# interlock_circuit.net
KiCad netlist of a schematic drawn in Altium Designer
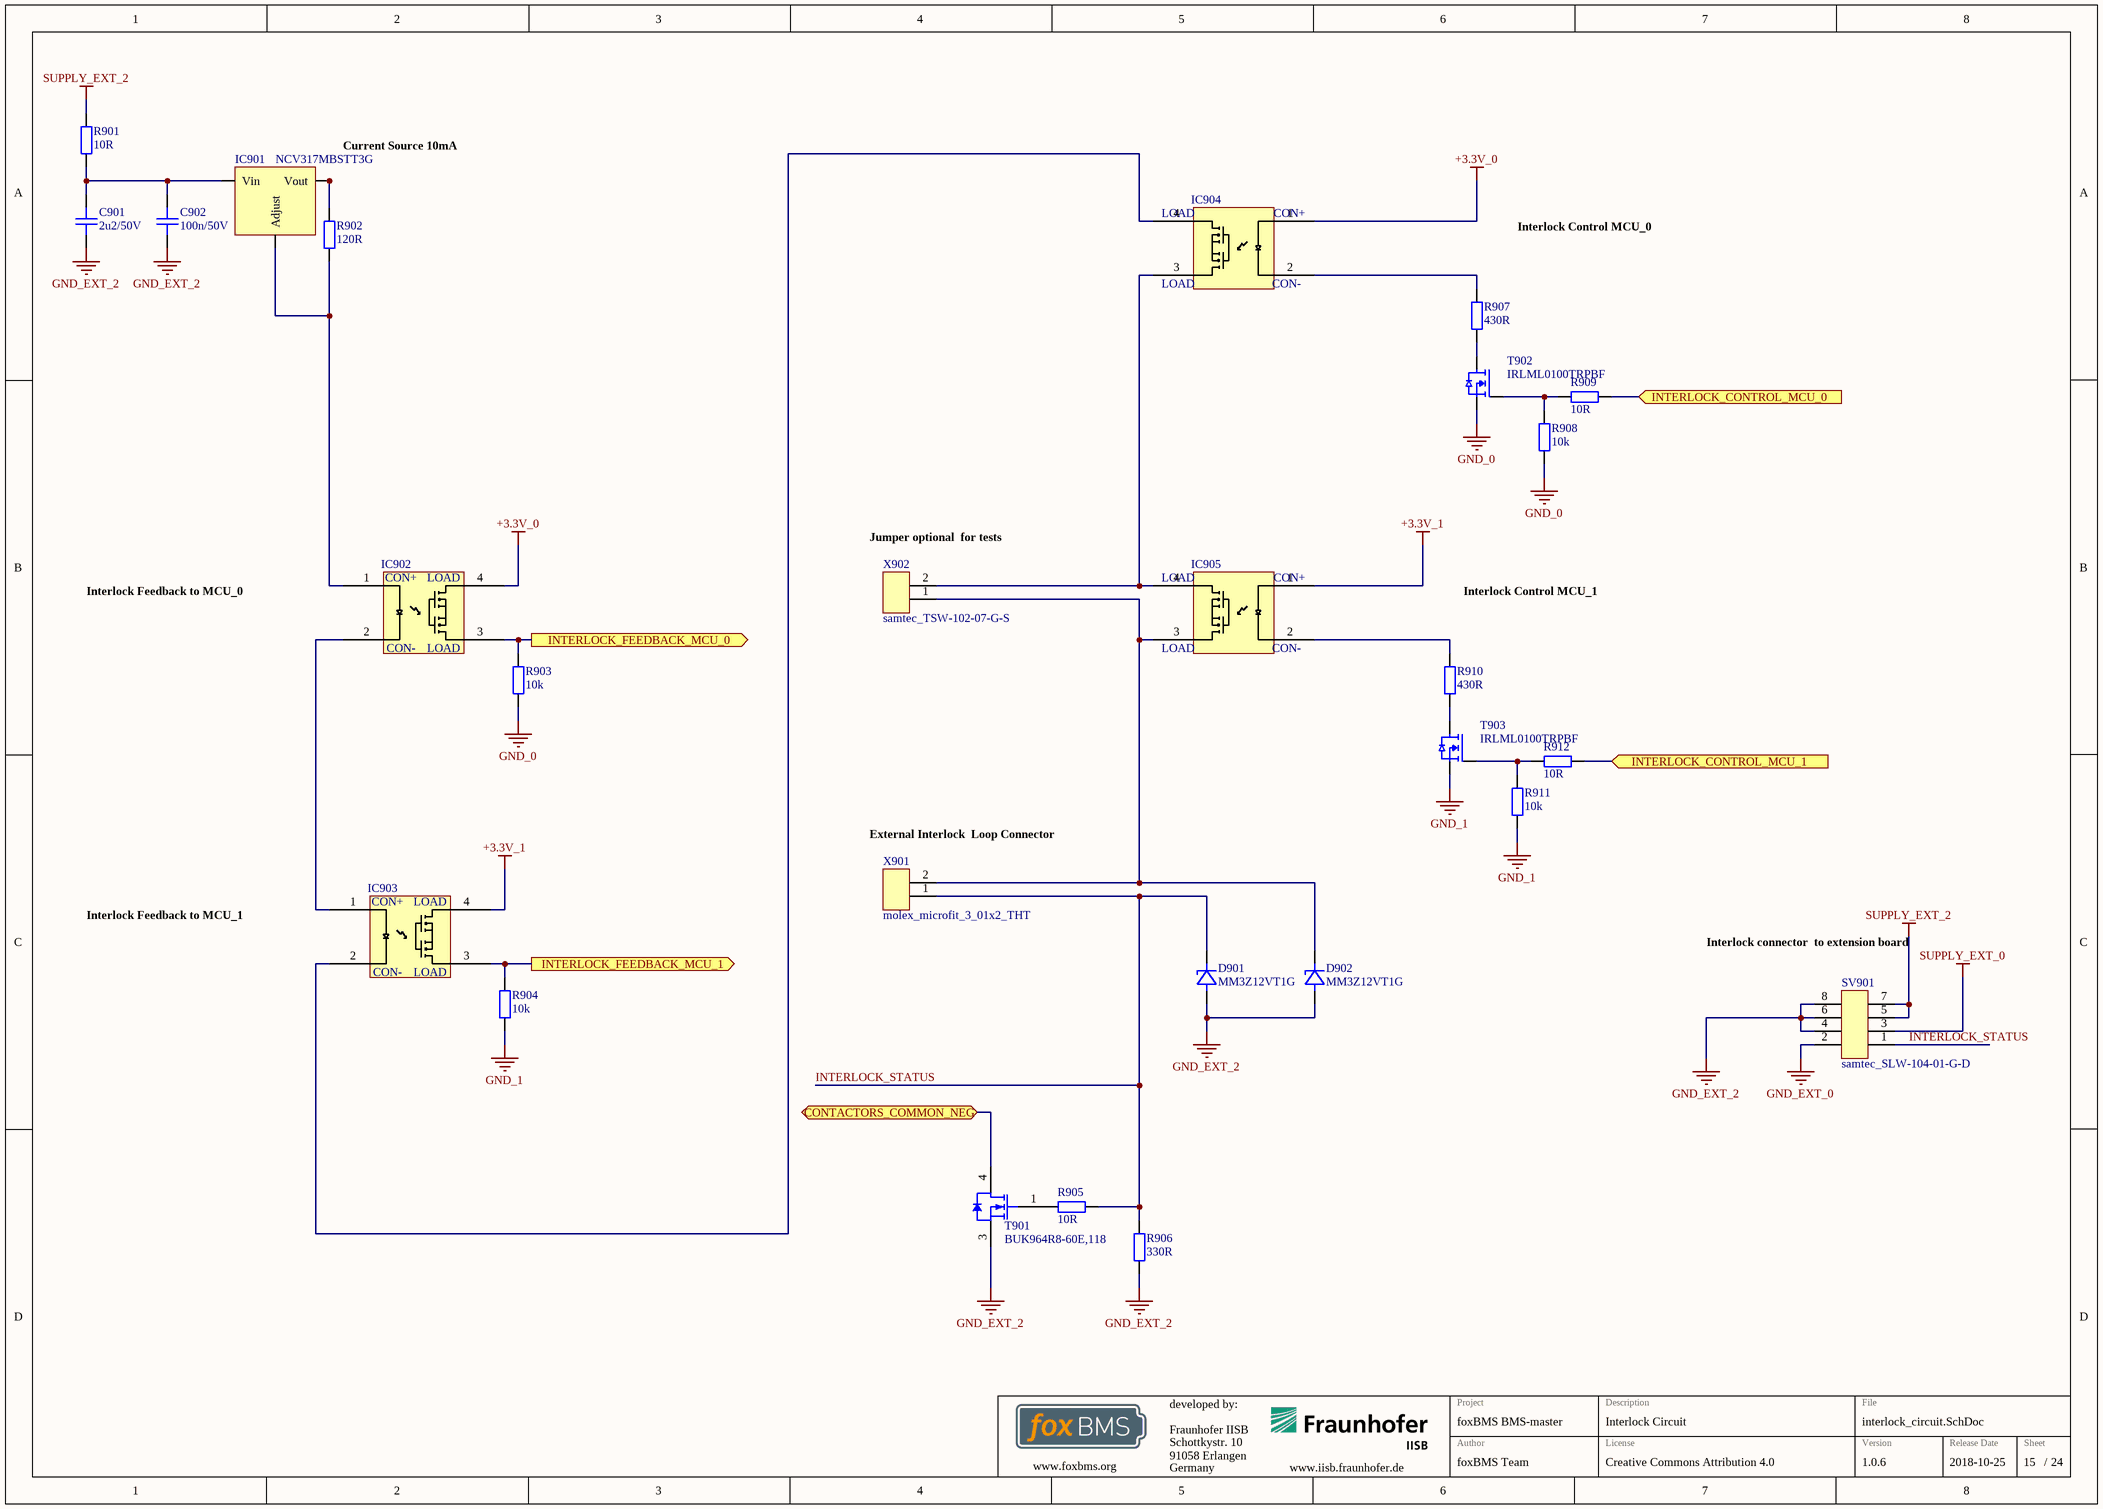
[diagram p0: interlock_circuit.SchDoc]

(export (version "E")
  (design (tool "Eeschema 10.0.6"))
  (components
    (comp (ref "C901")
      (value "2u2/50V")
      (footprint "CAPC2012X14N")
      (description "MLCC")
      (fields (field (name "PART NUMBER") "gen_C_ceramic_2u2_50V_X7R_0805"))
      (libsource (lib "OE750") (part "C"))
    )
    (comp (ref "C902")
      (value "100n/50V")
      (footprint "CAPC1608X08N")
      (description "MLCC")
      (fields (field (name "PART NUMBER") "gen_C_ceramic_100n_50V_X7R_0603"))
      (libsource (lib "OE750") (part "C"))
    )
    (comp (ref "D901")
      (value "MM3Z12VT1G")
      (footprint "SODFL250X110-2N")
      (description "Zener Diode")
      (fields (field (name "MANUFACTURER") "ON Semiconductor"))
      (libsource (lib "OE750") (part "D_Zener"))
    )
    (comp (ref "D902")
      (value "MM3Z12VT1G")
      (footprint "SODFL250X110-2N")
      (description "Zener Diode")
      (fields (field (name "MANUFACTURER") "ON Semiconductor"))
      (libsource (lib "OE750") (part "D_Zener"))
    )
    (comp (ref "IC901")
      (value "NCV317MBSTT3G")
      (footprint "SOT230P700X180-4N")
      (description "500mA Adjustable Output, Positive Voltage Regulator")
      (fields (field (name "MANUFACTURER") "ON Semiconductor"))
      (libsource (lib "OE750") (part "lin_volt_reg"))
    )
    (comp (ref "IC902")
      (value "CPC1008N")
      (footprint "SOP254P610X218-4N")
      (description "Single-Pole, Normally Open 4-Pin SOP OptoMOS Relay")
      (fields (field (name "MANUFACTURER") "CLARE"))
      (libsource (lib "OE750") (part "CPC1008N"))
    )
    (comp (ref "IC903")
      (value "CPC1008N")
      (footprint "SOP254P610X218-4N")
      (description "Single-Pole, Normally Open 4-Pin SOP OptoMOS Relay")
      (fields (field (name "MANUFACTURER") "CLARE"))
      (libsource (lib "OE750") (part "CPC1008N"))
    )
    (comp (ref "IC904")
      (value "CPC1008N")
      (footprint "SOP254P610X218-4N")
      (description "Single-Pole, Normally Open 4-Pin SOP OptoMOS Relay")
      (fields (field (name "MANUFACTURER") "CLARE"))
      (libsource (lib "") (part "CPC1008N_1"))
    )
    (comp (ref "IC905")
      (value "CPC1008N")
      (footprint "SOP254P610X218-4N")
      (description "Single-Pole, Normally Open 4-Pin SOP OptoMOS Relay")
      (fields (field (name "MANUFACTURER") "CLARE"))
      (libsource (lib "") (part "CPC1008N_1"))
    )
    (comp (ref "R901")
      (value "10R")
      (footprint "RESC1608X05N")
      (description "SMD Resistor 10R 0603")
      (fields (field (name "PART NUMBER") "gen_R_10R_0603") (field (name "TOLERANCE") "1%"))
      (libsource (lib "OE750") (part "R"))
    )
    (comp (ref "R902")
      (value "120R")
      (footprint "RESC1608X05N")
      (description "SMD Resistor 120R 0603")
      (fields (field (name "PART NUMBER") "gen_R_120R_0603") (field (name "TOLERANCE") "1%"))
      (libsource (lib "OE750") (part "R"))
    )
    (comp (ref "R903")
      (value "10k")
      (footprint "RESC1608X05N")
      (description "SMD Resistor 10k 0603")
      (fields (field (name "PART NUMBER") "gen_R_10k_0603") (field (name "TOLERANCE") "1%"))
      (libsource (lib "OE750") (part "R"))
    )
    (comp (ref "R904")
      (value "10k")
      (footprint "RESC1608X05N")
      (description "SMD Resistor 10k 0603")
      (fields (field (name "PART NUMBER") "gen_R_10k_0603") (field (name "TOLERANCE") "1%"))
      (libsource (lib "OE750") (part "R"))
    )
    (comp (ref "R905")
      (value "10R")
      (footprint "RESC1608X05N")
      (description "SMD Resistor 10R 0603")
      (fields (field (name "PART NUMBER") "gen_R_10R_0603") (field (name "TOLERANCE") "1%"))
      (libsource (lib "OE750") (part "R"))
    )
    (comp (ref "R906")
      (value "330R")
      (footprint "RESC1608X05N")
      (description "SMD Resistor 330R 0603")
      (fields (field (name "PART NUMBER") "gen_R_330R_0603") (field (name "TOLERANCE") "1%"))
      (libsource (lib "OE750") (part "R"))
    )
    (comp (ref "R907")
      (value "430R")
      (footprint "RESC1608X05N")
      (description "SMD Resistor 430R 0603")
      (fields (field (name "PART NUMBER") "gen_R_430R_0603") (field (name "TOLERANCE") "1%"))
      (libsource (lib "OE750") (part "R"))
    )
    (comp (ref "R908")
      (value "10k")
      (footprint "RESC1608X05N")
      (description "SMD Resistor 10k 0603")
      (fields (field (name "PART NUMBER") "gen_R_10k_0603") (field (name "TOLERANCE") "1%"))
      (libsource (lib "OE750") (part "R"))
    )
    (comp (ref "R909")
      (value "10R")
      (footprint "RESC1608X05N")
      (description "SMD Resistor 10R 0603")
      (fields (field (name "PART NUMBER") "gen_R_10R_0603") (field (name "TOLERANCE") "1%"))
      (libsource (lib "OE750") (part "R"))
    )
    (comp (ref "R910")
      (value "430R")
      (footprint "RESC1608X05N")
      (description "SMD Resistor 430R 0603")
      (fields (field (name "PART NUMBER") "gen_R_430R_0603") (field (name "TOLERANCE") "1%"))
      (libsource (lib "OE750") (part "R"))
    )
    (comp (ref "R911")
      (value "10k")
      (footprint "RESC1608X05N")
      (description "SMD Resistor 10k 0603")
      (fields (field (name "PART NUMBER") "gen_R_10k_0603") (field (name "TOLERANCE") "1%"))
      (libsource (lib "OE750") (part "R"))
    )
    (comp (ref "R912")
      (value "10R")
      (footprint "RESC1608X05N")
      (description "SMD Resistor 10R 0603")
      (fields (field (name "PART NUMBER") "gen_R_10R_0603") (field (name "TOLERANCE") "1%"))
      (libsource (lib "OE750") (part "R"))
    )
    (comp (ref "SV901")
      (value "samtec_SLW-104-01-G-D")
      (footprint "SLW_104_01_G_D")
      (description "Board-To-Board Connector, Dual, 2.54 mm, 8 Contacts, Receptacle, SLW Series, Through Hole, 2 Rows")
      (fields (field (name "MANUFACTURER") "Samtec"))
      (libsource (lib "OE750") (part "X2x4"))
    )
    (comp (ref "T901")
      (value "BUK964R8-60E,118")
      (footprint "NXP-SOT404_M")
      (description "N-Channel TrenchMOS Logic Level FET, 60 V, 100 A, 3-Pin SOT404, Tape and Reel")
      (fields (field (name "MANUFACTURER") "NXP Semiconductors"))
      (libsource (lib "Altium Content Vault") (part "NXP-NMOS-GSD-DPAK-3"))
    )
    (comp (ref "T902")
      (value "IRLML0100TRPBF")
      (footprint "SOT95P237X110-3N")
      (description "MOSFET-Transistor, n-Kanal, 1.6 A, 100 V, 0.178 ohm, 10 V, 2.5 V")
      (fields (field (name "MANUFACTURER") "Infineon"))
      (libsource (lib "OE750") (part "NMOS"))
    )
    (comp (ref "T903")
      (value "IRLML0100TRPBF")
      (footprint "SOT95P237X110-3N")
      (description "MOSFET-Transistor, n-Kanal, 1.6 A, 100 V, 0.178 ohm, 10 V, 2.5 V")
      (fields (field (name "MANUFACTURER") "Infineon"))
      (libsource (lib "OE750") (part "NMOS"))
    )
    (comp (ref "X901")
      (value "molex_microfit_3_01x2_THT")
      (footprint "MOLEX_MICROFIT_01x2_THT")
      (fields (field (name "MANUFACTURER") "Molex"))
      (libsource (lib "OE750") (part "X2"))
    )
    (comp (ref "X902")
      (value "samtec_TSW-102-07-G-S")
      (footprint "Pinheader_2.54_2")
      (description "Board-To-Board Connector, Vertical, 2.54 mm, 2 Contacts, Header, TSW Series, Through Hole, 1 Row")
      (fields (field (name "MANUFACTURER") "Samtec"))
      (libsource (lib "OE750") (part "X2"))
    )
  )
  (nets
    (net (code "1") (name "+3.3V_0") (class "Default")
      (node (ref "IC902") (pin "4") (pintype "passive"))
      (node (ref "IC904") (pin "1") (pintype "passive"))
    )
    (net (code "2") (name "+3.3V_1") (class "Default")
      (node (ref "IC903") (pin "4") (pintype "passive"))
      (node (ref "IC905") (pin "1") (pintype "passive"))
    )
    (net (code "3") (name "/CONTACTORS_COMMON_NEG") (class "Default")
      (node (ref "T901") (pin "4") (pinfunction "D_4") (pintype "passive"))
    )
    (net (code "4") (name "/INTERLOCK_CONTROL_MCU_0") (class "Default")
      (node (ref "R909") (pin "2") (pinfunction "2_2") (pintype "passive"))
    )
    (net (code "5") (name "/INTERLOCK_CONTROL_MCU_1") (class "Default")
      (node (ref "R912") (pin "2") (pinfunction "2_2") (pintype "passive"))
    )
    (net (code "6") (name "/INTERLOCK_FEEDBACK_MCU_0") (class "Default")
      (node (ref "IC902") (pin "3") (pintype "passive"))
      (node (ref "R903") (pin "2") (pinfunction "2_2") (pintype "passive"))
    )
    (net (code "7") (name "/INTERLOCK_FEEDBACK_MCU_1") (class "Default")
      (node (ref "IC903") (pin "3") (pintype "passive"))
      (node (ref "R904") (pin "2") (pinfunction "2_2") (pintype "passive"))
    )
    (net (code "8") (name "/INTERLOCK_STATUS") (class "Default")
      (node (ref "D901") (pin "1") (pinfunction "K_1") (pintype "passive"))
      (node (ref "R905") (pin "1") (pinfunction "1_1") (pintype "passive"))
      (node (ref "R906") (pin "2") (pinfunction "2_2") (pintype "passive"))
      (node (ref "SV901") (pin "1") (pintype "passive"))
      (node (ref "X901") (pin "1") (pintype "passive"))
    )
    (net (code "9") (name "GND_0") (class "Default")
      (node (ref "R903") (pin "1") (pinfunction "1_1") (pintype "passive"))
      (node (ref "R908") (pin "2") (pinfunction "2_2") (pintype "passive"))
      (node (ref "T902") (pin "S") (pinfunction "S_S") (pintype "passive"))
    )
    (net (code "10") (name "GND_1") (class "Default")
      (node (ref "R904") (pin "1") (pinfunction "1_1") (pintype "passive"))
      (node (ref "R911") (pin "2") (pinfunction "2_2") (pintype "passive"))
      (node (ref "T903") (pin "S") (pinfunction "S_S") (pintype "passive"))
    )
    (net (code "11") (name "GND_EXT_0") (class "Default") (node (ref "SV901") (pin "2") (pintype "passive")))
    (net (code "12") (name "GND_EXT_2") (class "Default")
      (node (ref "C901") (pin "2") (pinfunction "2_2") (pintype "passive"))
      (node (ref "C902") (pin "2") (pinfunction "2_2") (pintype "passive"))
      (node (ref "D901") (pin "2") (pinfunction "A_2") (pintype "passive"))
      (node (ref "D902") (pin "2") (pinfunction "A_2") (pintype "passive"))
      (node (ref "R906") (pin "1") (pinfunction "1_1") (pintype "passive"))
      (node (ref "SV901") (pin "4") (pintype "passive"))
      (node (ref "SV901") (pin "6") (pintype "passive"))
      (node (ref "SV901") (pin "8") (pintype "passive"))
      (node (ref "T901") (pin "3") (pinfunction "S_3") (pintype "passive"))
    )
    (net (code "13") (name "Net-(D902-K)") (class "Default")
      (node (ref "D902") (pin "1") (pinfunction "K_1") (pintype "passive"))
      (node (ref "IC905") (pin "3") (pintype "passive"))
      (node (ref "X901") (pin "2") (pintype "passive"))
      (node (ref "X902") (pin "1") (pintype "passive"))
    )
    (net (code "14") (name "Net-(IC901-Adjust)") (class "Default")
      (node (ref "IC901") (pin "1") (pinfunction "Adjust_1") (pintype "passive"))
      (node (ref "IC902") (pin "1") (pintype "passive"))
      (node (ref "R902") (pin "1") (pinfunction "1_1") (pintype "passive"))
    )
    (net (code "15") (name "Net-(IC901-Vin)") (class "Default")
      (node (ref "C901") (pin "1") (pinfunction "1_1") (pintype "passive"))
      (node (ref "C902") (pin "1") (pinfunction "1_1") (pintype "passive"))
      (node (ref "IC901") (pin "3") (pinfunction "Vin_3") (pintype "power_in"))
      (node (ref "R901") (pin "1") (pinfunction "1_1") (pintype "passive"))
    )
    (net (code "16") (name "Net-(IC901-Vout-Pad2)") (class "Default")
      (node (ref "IC901") (pin "2") (pinfunction "Vout_2") (pintype "power_in"))
      (node (ref "IC901") (pin "4") (pinfunction "Vout_4") (pintype "power_in"))
      (node (ref "R902") (pin "2") (pinfunction "2_2") (pintype "passive"))
    )
    (net (code "17") (name "Net-(IC902-Pad2)") (class "Default")
      (node (ref "IC902") (pin "2") (pintype "power_in"))
      (node (ref "IC903") (pin "1") (pintype "passive"))
    )
    (net (code "18") (name "Net-(IC903-Pad2)") (class "Default")
      (node (ref "IC903") (pin "2") (pintype "power_in"))
      (node (ref "IC904") (pin "4") (pintype "passive"))
    )
    (net (code "19") (name "Net-(IC904-Pad2)") (class "Default")
      (node (ref "IC904") (pin "2") (pintype "power_in"))
      (node (ref "R907") (pin "2") (pinfunction "2_2") (pintype "passive"))
    )
    (net (code "20") (name "Net-(IC904-Pad3)") (class "Default")
      (node (ref "IC904") (pin "3") (pintype "passive"))
      (node (ref "IC905") (pin "4") (pintype "passive"))
      (node (ref "X902") (pin "2") (pintype "passive"))
    )
    (net (code "21") (name "Net-(IC905-Pad2)") (class "Default")
      (node (ref "IC905") (pin "2") (pintype "power_in"))
      (node (ref "R910") (pin "2") (pinfunction "2_2") (pintype "passive"))
    )
    (net (code "22") (name "Net-(R907-Pad1)") (class "Default")
      (node (ref "R907") (pin "1") (pinfunction "1_1") (pintype "passive"))
      (node (ref "T902") (pin "D") (pinfunction "D_D") (pintype "passive"))
    )
    (net (code "23") (name "Net-(R908-Pad1)") (class "Default")
      (node (ref "R908") (pin "1") (pinfunction "1_1") (pintype "passive"))
      (node (ref "R909") (pin "1") (pinfunction "1_1") (pintype "passive"))
      (node (ref "T902") (pin "G") (pinfunction "G_G") (pintype "passive"))
    )
    (net (code "24") (name "Net-(R910-Pad1)") (class "Default")
      (node (ref "R910") (pin "1") (pinfunction "1_1") (pintype "passive"))
      (node (ref "T903") (pin "D") (pinfunction "D_D") (pintype "passive"))
    )
    (net (code "25") (name "Net-(R911-Pad1)") (class "Default")
      (node (ref "R911") (pin "1") (pinfunction "1_1") (pintype "passive"))
      (node (ref "R912") (pin "1") (pinfunction "1_1") (pintype "passive"))
      (node (ref "T903") (pin "G") (pinfunction "G_G") (pintype "passive"))
    )
    (net (code "26") (name "Net-(T901-G)") (class "Default")
      (node (ref "R905") (pin "2") (pinfunction "2_2") (pintype "passive"))
      (node (ref "T901") (pin "1") (pinfunction "G_1") (pintype "passive"))
    )
    (net (code "27") (name "SUPPLY_EXT_0") (class "Default")
      (node (ref "SV901") (pin "3") (pintype "passive"))
    )
    (net (code "28") (name "SUPPLY_EXT_2") (class "Default")
      (node (ref "R901") (pin "2") (pinfunction "2_2") (pintype "passive"))
      (node (ref "SV901") (pin "5") (pintype "passive"))
      (node (ref "SV901") (pin "7") (pintype "passive"))
    )
  )
)
